# blinkenbytes_sch_altium_design.net
KiCad netlist of a schematic drawn in Altium Designer
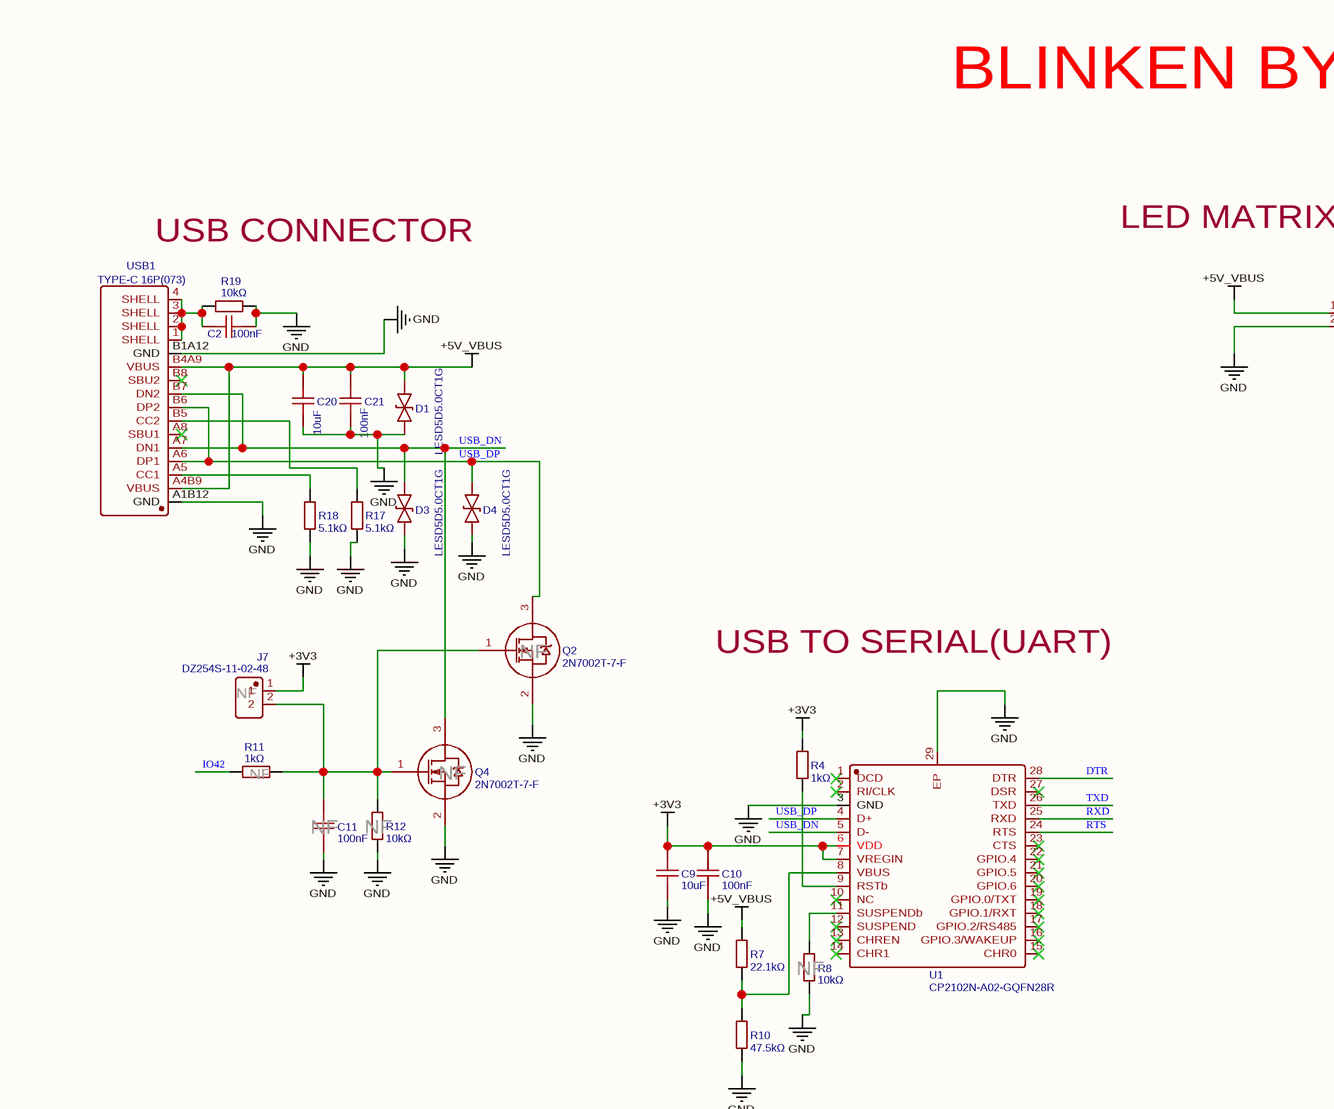
[diagram p0: blinkenbytes_sch_altium design.schdoc, top left]
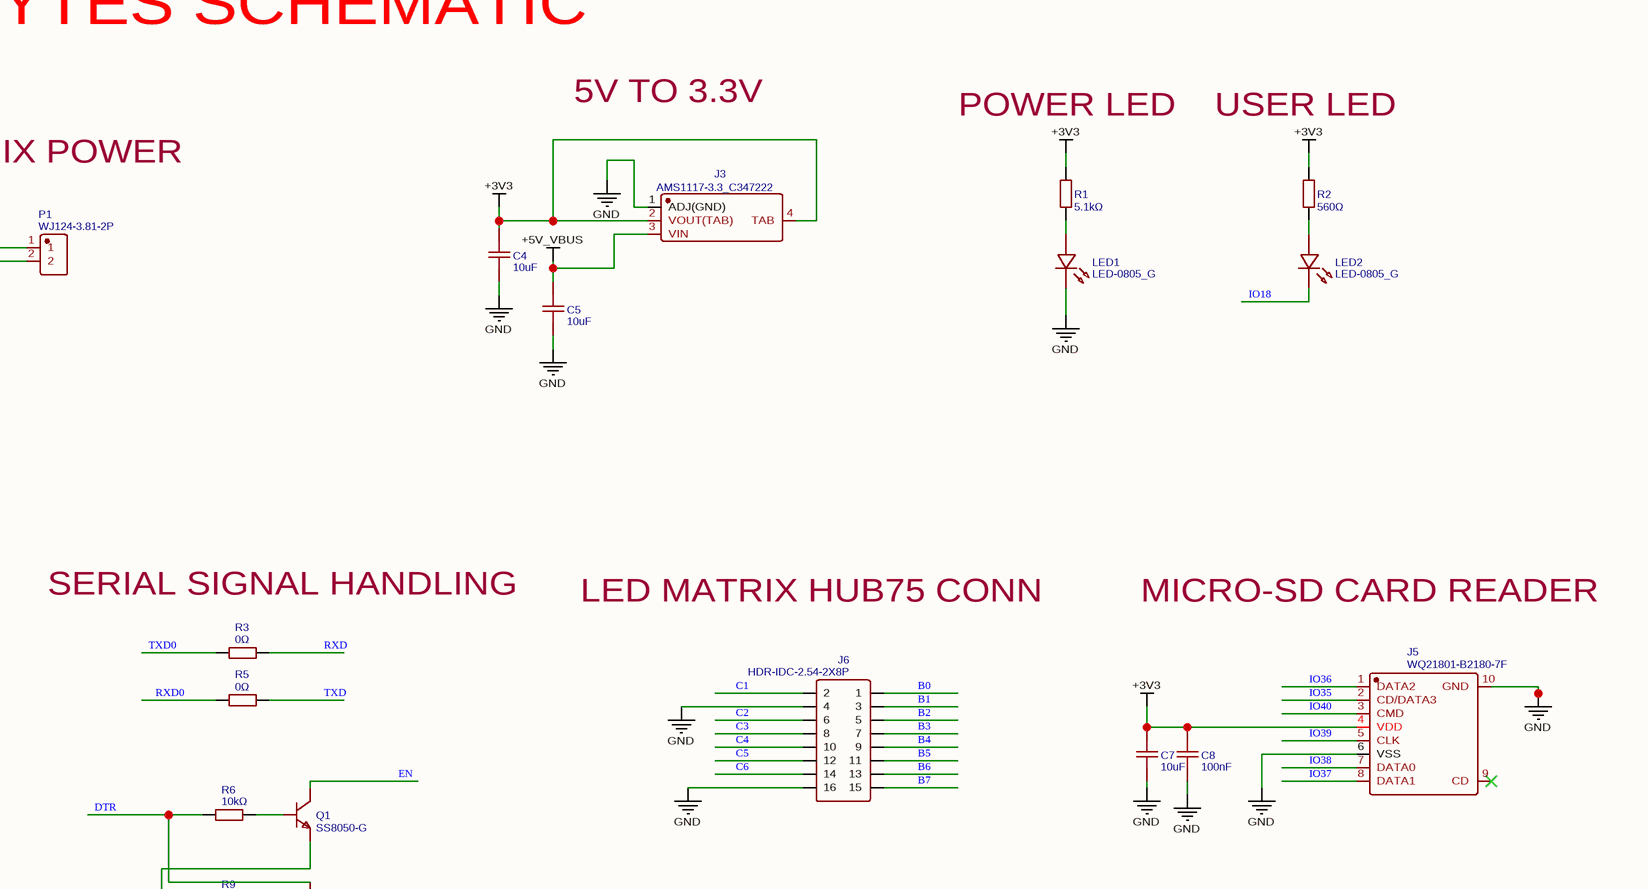
[diagram p1: blinkenbytes_sch_altium design.schdoc, top right]
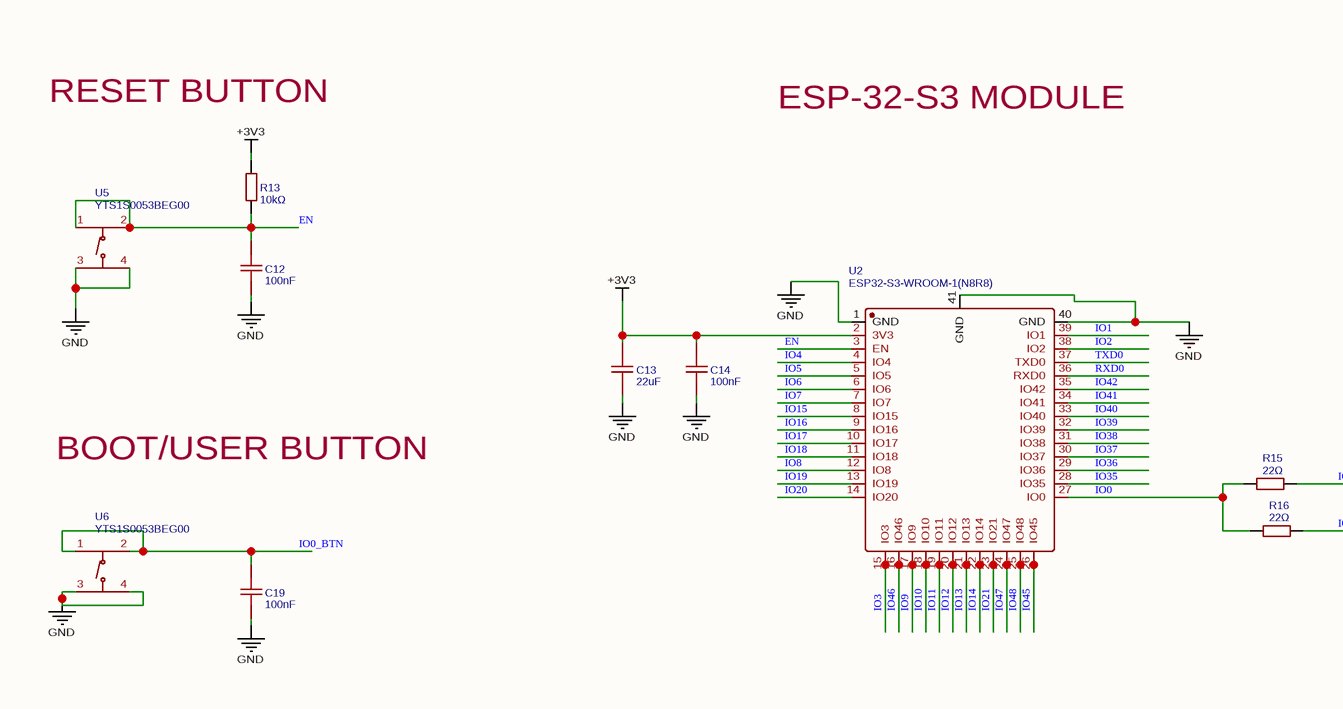
[diagram p2: blinkenbytes_sch_altium design.schdoc, bottom left]
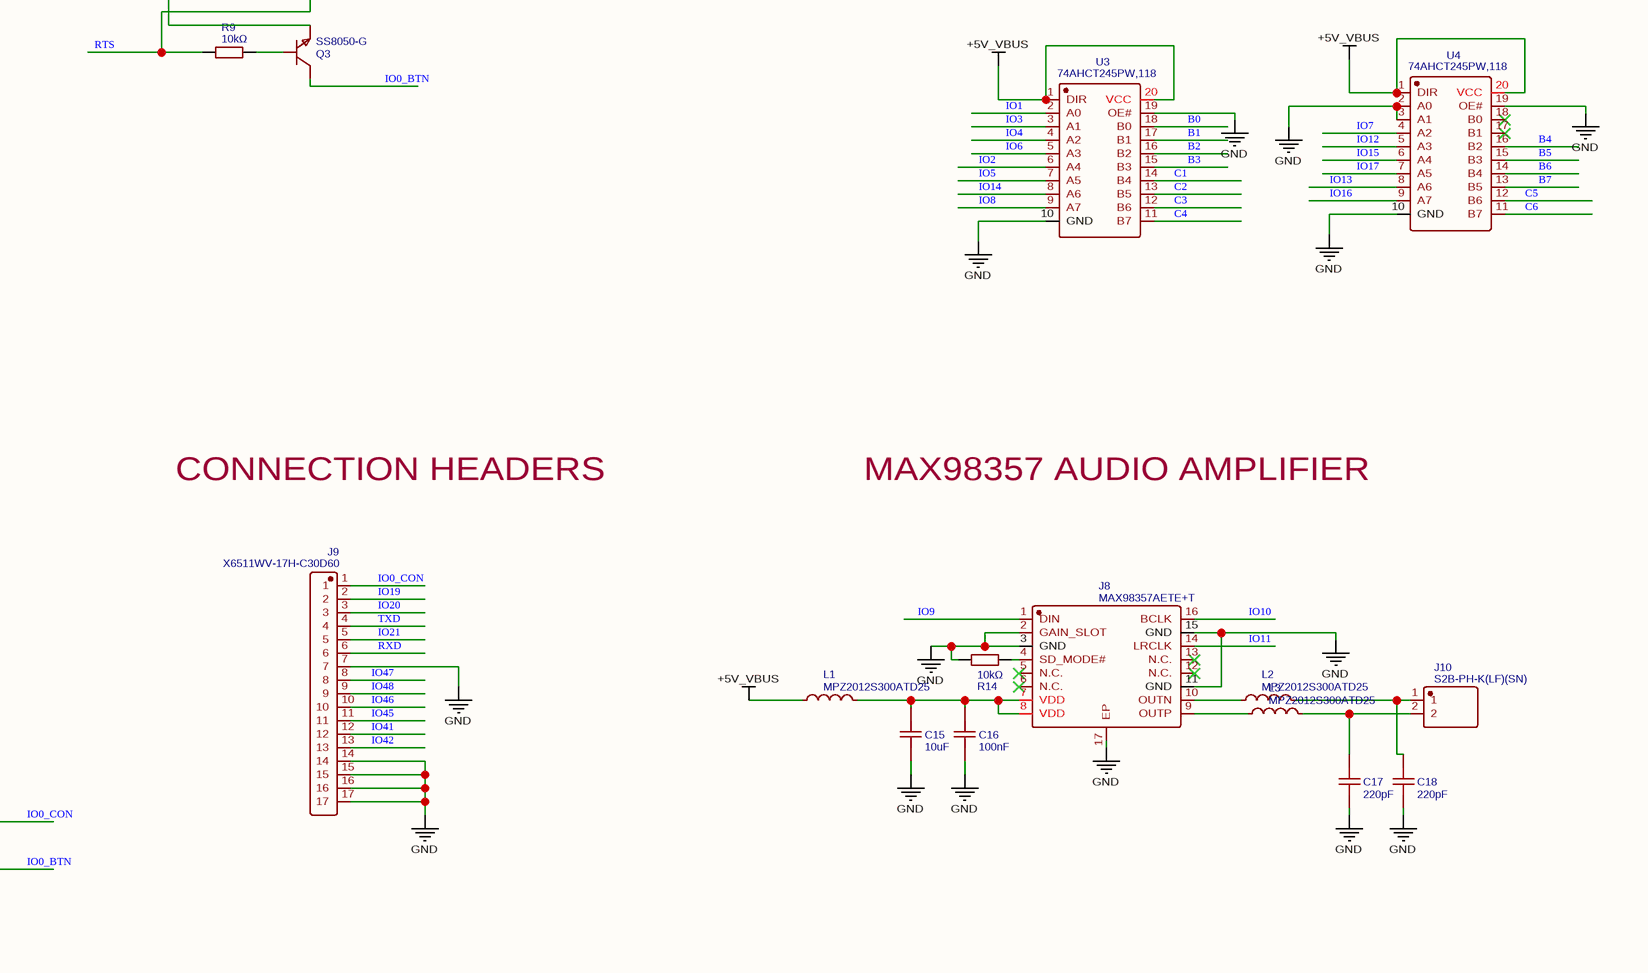
[diagram p3: blinkenbytes_sch_altium design.schdoc, bottom right]

(export (version "E")
  (design (tool "Eeschema 10.0.6"))
  (components
    (comp (ref "C2")
      (value "100nF")
      (fields
        (field (name "MANUFACTURER") "SAMSUNG(三星)")
        (field (name "MANUFACTURER PART") "CL21B104KBFWPJE")
        (field (name "CONTRIBUTOR") "lcsc")
      )
      (libsource (lib "altium-import") (part "root_0_100nF_"))
    )
    (comp (ref "C4")
      (value "10uF")
      (fields
        (field (name "MANUFACTURER") "SAMSUNG(三星)")
        (field (name "MANUFACTURER PART") "CL05A106MP5NUNC")
        (field (name "CONTRIBUTOR") "LCSC")
      )
      (libsource (lib "altium-import") (part "root_1_10uF_"))
    )
    (comp (ref "C5")
      (value "10uF")
      (fields
        (field (name "MANUFACTURER") "SAMSUNG(三星)")
        (field (name "MANUFACTURER PART") "CL05A106MP5NUNC")
        (field (name "CONTRIBUTOR") "LCSC")
      )
      (libsource (lib "altium-import") (part "root_1_10uF_"))
    )
    (comp (ref "C7")
      (value "10uF")
      (fields
        (field (name "MANUFACTURER") "SAMSUNG(三星)")
        (field (name "MANUFACTURER PART") "CL05A106MP5NUNC")
        (field (name "CONTRIBUTOR") "LCSC")
      )
      (libsource (lib "altium-import") (part "root_1_10uF_"))
    )
    (comp (ref "C8")
      (value "100nF")
      (fields
        (field (name "MANUFACTURER PART") "CL05B104KO5NNNC")
        (field (name "MANUFACTURER") "SAMSUNG(三星)")
      )
      (libsource (lib "altium-import") (part "root_1_100nF_"))
    )
    (comp (ref "C9")
      (value "10uF")
      (fields
        (field (name "MANUFACTURER") "SAMSUNG(三星)")
        (field (name "MANUFACTURER PART") "CL05A106MP5NUNC")
        (field (name "CONTRIBUTOR") "LCSC")
      )
      (libsource (lib "altium-import") (part "root_1_10uF_"))
    )
    (comp (ref "C10")
      (value "100nF")
      (fields
        (field (name "MANUFACTURER PART") "CL05B104KO5NNNC")
        (field (name "MANUFACTURER") "SAMSUNG(三星)")
      )
      (libsource (lib "altium-import") (part "root_1_100nF_"))
    )
    (comp (ref "C11")
      (value "100nF")
      (fields
        (field (name "MANUFACTURER PART") "CL05B104KO5NNNC")
        (field (name "MANUFACTURER") "SAMSUNG(三星)")
      )
      (libsource (lib "altium-import") (part "root_1_100nF_"))
    )
    (comp (ref "C12")
      (value "100nF")
      (fields
        (field (name "MANUFACTURER PART") "CL05B104KO5NNNC")
        (field (name "MANUFACTURER") "SAMSUNG(三星)")
      )
      (libsource (lib "altium-import") (part "root_1_100nF_"))
    )
    (comp (ref "C13")
      (value "22uF")
      (fields
        (field (name "MANUFACTURER") "SAMSUNG(三星)")
        (field (name "MANUFACTURER PART") "CL21A226MAQNNNE")
      )
      (libsource (lib "altium-import") (part "root_1_22uF_"))
    )
    (comp (ref "C14")
      (value "100nF")
      (fields
        (field (name "MANUFACTURER PART") "CL05B104KO5NNNC")
        (field (name "MANUFACTURER") "SAMSUNG(三星)")
      )
      (libsource (lib "altium-import") (part "root_1_100nF_"))
    )
    (comp (ref "C15")
      (value "10uF")
      (fields
        (field (name "MANUFACTURER") "SAMSUNG(三星)")
        (field (name "MANUFACTURER PART") "CL21B106KAYQNNE")
        (field (name "CONTRIBUTOR") "lcsc")
      )
      (libsource (lib "altium-import") (part "root_1_10uF_"))
    )
    (comp (ref "C16")
      (value "100nF")
      (fields
        (field (name "MANUFACTURER") "SAMSUNG(三星)")
        (field (name "MANUFACTURER PART") "CL21B104KBFWPJE")
        (field (name "CONTRIBUTOR") "lcsc")
      )
      (libsource (lib "altium-import") (part "root_1_100nF_"))
    )
    (comp (ref "C17")
      (value "220pF")
      (fields
        (field (name "MANUFACTURER") "Kyocera AVX")
        (field (name "MANUFACTURER PART") "04025A221JAT2A")
        (field (name "CONTRIBUTOR") "LCSC")
      )
      (libsource (lib "altium-import") (part "root_1_220pF_"))
    )
    (comp (ref "C18")
      (value "220pF")
      (fields
        (field (name "MANUFACTURER") "Kyocera AVX")
        (field (name "MANUFACTURER PART") "04025A221JAT2A")
        (field (name "CONTRIBUTOR") "LCSC")
      )
      (libsource (lib "altium-import") (part "root_1_220pF_"))
    )
    (comp (ref "C19")
      (value "100nF")
      (fields
        (field (name "MANUFACTURER PART") "CL05B104KO5NNNC")
        (field (name "MANUFACTURER") "SAMSUNG(三星)")
      )
      (libsource (lib "altium-import") (part "root_1_100nF_"))
    )
    (comp (ref "C20")
      (value "10uF")
      (fields
        (field (name "MANUFACTURER") "SAMSUNG(三星)")
        (field (name "MANUFACTURER PART") "CL21B106KAYQNNE")
        (field (name "CONTRIBUTOR") "lcsc")
      )
      (libsource (lib "altium-import") (part "root_1_10uF_"))
    )
    (comp (ref "C21")
      (value "100nF")
      (fields
        (field (name "MANUFACTURER") "SAMSUNG(三星)")
        (field (name "MANUFACTURER PART") "CL21B104KBFWPJE")
        (field (name "CONTRIBUTOR") "lcsc")
      )
      (libsource (lib "altium-import") (part "root_1_100nF_"))
    )
    (comp (ref "D1")
      (value "LESD5D5.0CT1G")
      (fields (field (name "MANUFACTURER") "LRC(乐山无线电)") (field (name "CONTRIBUTOR") "LCSC"))
      (libsource (lib "altium-import") (part "root_1_LESD5D5.0CT1G_"))
    )
    (comp (ref "D3")
      (value "LESD5D5.0CT1G")
      (fields (field (name "MANUFACTURER") "LRC(乐山无线电)") (field (name "CONTRIBUTOR") "LCSC"))
      (libsource (lib "altium-import") (part "root_1_LESD5D5.0CT1G_"))
    )
    (comp (ref "D4")
      (value "LESD5D5.0CT1G")
      (fields (field (name "MANUFACTURER") "LRC(乐山无线电)") (field (name "CONTRIBUTOR") "LCSC"))
      (libsource (lib "altium-import") (part "root_1_LESD5D5.0CT1G_"))
    )
    (comp (ref "J3")
      (value "AMS1117-3.3_C347222")
      (fields
        (field (name "MANUFACTURER") "UMW(友台半导体)")
        (field (name "MANUFACTURER PART") "AMS1117-3.3")
        (field (name "CONTRIBUTOR") "LCSC")
      )
      (libsource (lib "altium-import") (part "root_0_AMS1117-3.3_C347222_"))
    )
    (comp (ref "J5")
      (value "WQ21801-B2180-7F")
      (fields (field (name "MANUFACTURER") "FOXCONN(富士康)") (field (name "CONTRIBUTOR") "LCSC"))
      (libsource (lib "altium-import") (part "root_0_WQ21801-B2180-7F_"))
    )
    (comp (ref "J6")
      (value "HDR-IDC-2.54-2X8P")
      (fields (field (name "MANUFACTURER") "BOOMELE(博穆精密)") (field (name "MANUFACTURER PART") "2.54-2*8P简牛"))
      (libsource (lib "altium-import") (part "root_0_HDR-IDC-2.54-2X8P_"))
    )
    (comp (ref "J7")
      (value "DZ254S-11-02-48")
      (fields (field (name "MANUFACTURER") "DEALON(德艺隆)") (field (name "CONTRIBUTOR") "lcsc"))
      (libsource (lib "altium-import") (part "root_0_DZ254S-11-02-48_"))
    )
    (comp (ref "J8")
      (value "MAX98357AETE+T")
      (fields (field (name "MANUFACTURER") "ADI(亚德诺)/MAXIM(美信)") (field (name "CONTRIBUTOR") "LCSC"))
      (libsource (lib "altium-import") (part "root_0_MAX98357AETE+T_"))
    )
    (comp (ref "J9")
      (value "X6511WV-17H-C30D60")
      (fields
        (field (name "MANUFACTURER") "XKB Connection(中国星坤)")
        (field (name "MANUFACTURER PART") "X6511WV-17H-C60D30")
        (field (name "CONTRIBUTOR") "LCSC")
      )
      (libsource (lib "altium-import") (part "root_0_X6511WV-17H-C30D60_"))
    )
    (comp (ref "J10")
      (value "S2B-PH-K(LF)(SN)")
      (fields (field (name "MANUFACTURER") "JST") (field (name "CONTRIBUTOR") "LCSC"))
      (libsource (lib "altium-import") (part "root_0_S2B-PH-K(LF)(SN)_"))
    )
    (comp (ref "L1")
      (value "MPZ2012S300ATD25")
      (fields (field (name "MANUFACTURER") "TDK") (field (name "CONTRIBUTOR") "LCSC"))
      (libsource (lib "altium-import") (part "root_0_MPZ2012S300ATD25_"))
    )
    (comp (ref "L2")
      (value "MPZ2012S300ATD25")
      (fields (field (name "MANUFACTURER") "TDK") (field (name "CONTRIBUTOR") "LCSC"))
      (libsource (lib "altium-import") (part "root_0_MPZ2012S300ATD25_"))
    )
    (comp (ref "L3")
      (value "MPZ2012S300ATD25")
      (fields (field (name "MANUFACTURER") "TDK") (field (name "CONTRIBUTOR") "LCSC"))
      (libsource (lib "altium-import") (part "root_0_MPZ2012S300ATD25_"))
    )
    (comp (ref "LED1")
      (value "LED-0805_G")
      (fields
        (field (name "MANUFACTURER") "国星光电")
        (field (name "MANUFACTURER PART") "NCD0805G1")
        (field (name "CONTRIBUTOR") "LCEDA_Lib")
      )
      (libsource (lib "altium-import") (part "root_3_LED-0805_G_"))
    )
    (comp (ref "LED2")
      (value "LED-0805_G")
      (fields
        (field (name "MANUFACTURER") "国星光电")
        (field (name "MANUFACTURER PART") "NCD0805G1")
        (field (name "CONTRIBUTOR") "LCEDA_Lib")
      )
      (libsource (lib "altium-import") (part "root_3_LED-0805_G_"))
    )
    (comp (ref "P1")
      (value "WJ124-3.81-2P")
      (fields (field (name "MANUFACTURER") "KANGNEX(康奈克斯电气)"))
      (libsource (lib "altium-import") (part "root_0_WJ124-3.81-2P_"))
    )
    (comp (ref "Q1")
      (value "SS8050-G")
      (fields
        (field (name "MANUFACTURER") "CJ(江苏长电/长晶)")
        (field (name "MANUFACTURER PART") "SS8050-G(RANGE:120-200)")
        (field (name "CONTRIBUTOR") "LCSC")
      )
      (libsource (lib "altium-import") (part "root_0_SS8050-G_"))
    )
    (comp (ref "Q2")
      (value "2N7002T-7-F")
      (fields (field (name "MANUFACTURER") "DIODES(美台)") (field (name "CONTRIBUTOR") "LCSC"))
      (libsource (lib "altium-import") (part "root_0_2N7002T-7-F_"))
    )
    (comp (ref "Q3")
      (value "SS8050-G")
      (fields
        (field (name "MANUFACTURER") "CJ(江苏长电/长晶)")
        (field (name "MANUFACTURER PART") "SS8050-G(RANGE:120-200)")
        (field (name "CONTRIBUTOR") "LCSC")
      )
      (libsource (lib "") (part "root_0_SS8050-G__1"))
    )
    (comp (ref "Q4")
      (value "2N7002T-7-F")
      (fields (field (name "MANUFACTURER") "DIODES(美台)") (field (name "CONTRIBUTOR") "LCSC"))
      (libsource (lib "altium-import") (part "root_0_2N7002T-7-F_"))
    )
    (comp (ref "R1")
      (value "5.1kΩ")
      (fields
        (field (name "MANUFACTURER") "UNI-ROYAL(厚声)")
        (field (name "MANUFACTURER PART") "0402WGF5101TCE")
      )
      (libsource (lib "altium-import") (part "root_1_5.1kΩ_"))
    )
    (comp (ref "R2")
      (value "560Ω")
      (fields
        (field (name "MANUFACTURER") "UNI-ROYAL(厚声)")
        (field (name "MANUFACTURER PART") "0402WGF5600TCE")
      )
      (libsource (lib "altium-import") (part "root_1_560Ω_"))
    )
    (comp (ref "R3")
      (value "0Ω")
      (fields
        (field (name "MANUFACTURER") "UNI-ROYAL(厚声)")
        (field (name "MANUFACTURER PART") "0402WGF0000TCE")
      )
      (libsource (lib "altium-import") (part "root_0_0Ω_"))
    )
    (comp (ref "R4")
      (value "1kΩ")
      (fields
        (field (name "MANUFACTURER") "UNI-ROYAL(厚声)")
        (field (name "MANUFACTURER PART") "0402WGF1001TCE")
      )
      (libsource (lib "altium-import") (part "root_1_1kΩ_"))
    )
    (comp (ref "R5")
      (value "0Ω")
      (fields
        (field (name "MANUFACTURER") "UNI-ROYAL(厚声)")
        (field (name "MANUFACTURER PART") "0402WGF0000TCE")
      )
      (libsource (lib "altium-import") (part "root_0_0Ω_"))
    )
    (comp (ref "R6")
      (value "10kΩ")
      (fields
        (field (name "MANUFACTURER") "UNI-ROYAL(厚声)")
        (field (name "MANUFACTURER PART") "0402WGF1002TCE")
      )
      (libsource (lib "altium-import") (part "root_0_10kΩ_"))
    )
    (comp (ref "R7")
      (value "22.1kΩ")
      (fields
        (field (name "MANUFACTURER") "UNI-ROYAL(厚声)")
        (field (name "MANUFACTURER PART") "0402WGF2212TCE")
      )
      (libsource (lib "altium-import") (part "root_1_22.1kΩ_"))
    )
    (comp (ref "R8")
      (value "10kΩ")
      (fields
        (field (name "MANUFACTURER") "UNI-ROYAL(厚声)")
        (field (name "MANUFACTURER PART") "0402WGF1002TCE")
      )
      (libsource (lib "altium-import") (part "root_3_10kΩ_"))
    )
    (comp (ref "R9")
      (value "10kΩ")
      (fields
        (field (name "MANUFACTURER") "UNI-ROYAL(厚声)")
        (field (name "MANUFACTURER PART") "0402WGF1002TCE")
      )
      (libsource (lib "altium-import") (part "root_0_10kΩ_"))
    )
    (comp (ref "R10")
      (value "47.5kΩ")
      (fields
        (field (name "MANUFACTURER") "UNI-ROYAL(厚声)")
        (field (name "MANUFACTURER PART") "0402WGF4752TCE")
      )
      (libsource (lib "altium-import") (part "root_1_47.5kΩ_"))
    )
    (comp (ref "R11")
      (value "1kΩ")
      (fields
        (field (name "MANUFACTURER") "UNI-ROYAL(厚声)")
        (field (name "MANUFACTURER PART") "0402WGF1001TCE")
      )
      (libsource (lib "altium-import") (part "root_2_1kΩ_"))
    )
    (comp (ref "R12")
      (value "10kΩ")
      (fields
        (field (name "MANUFACTURER") "UNI-ROYAL(厚声)")
        (field (name "MANUFACTURER PART") "0402WGF1002TCE")
      )
      (libsource (lib "altium-import") (part "root_3_10kΩ_"))
    )
    (comp (ref "R13")
      (value "10kΩ")
      (fields
        (field (name "MANUFACTURER") "UNI-ROYAL(厚声)")
        (field (name "MANUFACTURER PART") "0402WGF1002TCE")
      )
      (libsource (lib "altium-import") (part "root_1_10kΩ_"))
    )
    (comp (ref "R14")
      (value "10kΩ")
      (fields
        (field (name "MANUFACTURER") "UNI-ROYAL(厚声)")
        (field (name "MANUFACTURER PART") "0402WGF1002TCE")
      )
      (libsource (lib "altium-import") (part "root_0_10kΩ_"))
    )
    (comp (ref "R15")
      (value "22Ω")
      (fields
        (field (name "MANUFACTURER") "UNI-ROYAL(厚声)")
        (field (name "MANUFACTURER PART") "0402WGF220JTCE")
      )
      (libsource (lib "altium-import") (part "root_0_22Ω_"))
    )
    (comp (ref "R16")
      (value "22Ω")
      (fields
        (field (name "MANUFACTURER") "UNI-ROYAL(厚声)")
        (field (name "MANUFACTURER PART") "0402WGF220JTCE")
      )
      (libsource (lib "altium-import") (part "root_0_22Ω_"))
    )
    (comp (ref "R17")
      (value "5.1kΩ")
      (fields
        (field (name "MANUFACTURER") "UNI-ROYAL(厚声)")
        (field (name "MANUFACTURER PART") "0402WGF5101TCE")
      )
      (libsource (lib "altium-import") (part "root_1_5.1kΩ_"))
    )
    (comp (ref "R18")
      (value "5.1kΩ")
      (fields
        (field (name "MANUFACTURER") "UNI-ROYAL(厚声)")
        (field (name "MANUFACTURER PART") "0402WGF5101TCE")
      )
      (libsource (lib "altium-import") (part "root_1_5.1kΩ_"))
    )
    (comp (ref "R19")
      (value "10kΩ")
      (fields
        (field (name "MANUFACTURER") "UNI-ROYAL(厚声)")
        (field (name "MANUFACTURER PART") "0603WAF1002T5E")
      )
      (libsource (lib "altium-import") (part "root_0_10kΩ_"))
    )
    (comp (ref "U1")
      (value "CP2102N-A02-GQFN28R")
      (fields (field (name "MANUFACTURER") "SKYWORKS/SILICON LABS(芯科)") (field (name "CONTRIBUTOR") "LCSC"))
      (libsource (lib "altium-import") (part "root_0_CP2102N-A02-GQFN28R_"))
    )
    (comp (ref "U2")
      (value "ESP32-S3-WROOM-1(N8R8)")
      (fields
        (field (name "MANUFACTURER") "ESPRESSIF(乐鑫)")
        (field (name "MANUFACTURER PART") "ESP32-S3-WROOM-1-N8R8")
        (field (name "CONTRIBUTOR") "LCSC")
      )
      (libsource (lib "altium-import") (part "root_0_ESP32-S3-WROOM-1(N8R8)_"))
    )
    (comp (ref "U3")
      (value "74AHCT245PW,118")
      (fields (field (name "MANUFACTURER") "Nexperia(安世)") (field (name "CONTRIBUTOR") "LCSC"))
      (libsource (lib "altium-import") (part "root_0_74AHCT245PW,118_"))
    )
    (comp (ref "U4")
      (value "74AHCT245PW,118")
      (fields (field (name "MANUFACTURER") "Nexperia(安世)") (field (name "CONTRIBUTOR") "LCSC"))
      (libsource (lib "altium-import") (part "root_0_74AHCT245PW,118_"))
    )
    (comp (ref "U5")
      (value "YTS1S0053BEG00")
      (fields (field (name "MANUFACTURER") "YIYUAN(怡远)") (field (name "CONTRIBUTOR") "lcsc"))
      (libsource (lib "altium-import") (part "root_0_YTS1S0053BEG00_"))
    )
    (comp (ref "U6")
      (value "YTS1S0053BEG00")
      (fields (field (name "MANUFACTURER") "YIYUAN(怡远)") (field (name "CONTRIBUTOR") "lcsc"))
      (libsource (lib "altium-import") (part "root_0_YTS1S0053BEG00_"))
    )
    (comp (ref "USB1")
      (value "TYPE-C 16P(073)")
      (fields (field (name "MANUFACTURER") "SHOU HAN(首韩)") (field (name "CONTRIBUTOR") "LCSC"))
      (libsource (lib "altium-import") (part "root_2_TYPE-C 16P(073)_"))
    )
  )
  (nets
    (net (code "1") (name "+3V3") (class "Default")
      (node (ref "C10") (pin "2") (pinfunction "2_2") (pintype "passive"))
      (node (ref "C13") (pin "2") (pinfunction "2_2") (pintype "passive"))
      (node (ref "C14") (pin "2") (pinfunction "2_2") (pintype "passive"))
      (node (ref "C4") (pin "2") (pinfunction "2_2") (pintype "passive"))
      (node (ref "C7") (pin "2") (pinfunction "2_2") (pintype "passive"))
      (node (ref "C8") (pin "2") (pinfunction "2_2") (pintype "passive"))
      (node (ref "C9") (pin "2") (pinfunction "2_2") (pintype "passive"))
      (node (ref "J3") (pin "2") (pinfunction "VOUT(TAB)_2") (pintype "passive"))
      (node (ref "J3") (pin "4") (pinfunction "TAB_4") (pintype "passive"))
      (node (ref "J5") (pin "4") (pinfunction "VDD_4") (pintype "passive"))
      (node (ref "J7") (pin "1") (pinfunction "1_1") (pintype "passive"))
      (node (ref "R1") (pin "2") (pinfunction "2_2") (pintype "passive"))
      (node (ref "R13") (pin "2") (pinfunction "2_2") (pintype "passive"))
      (node (ref "R2") (pin "2") (pinfunction "2_2") (pintype "passive"))
      (node (ref "R4") (pin "2") (pinfunction "2_2") (pintype "passive"))
      (node (ref "U1") (pin "6") (pinfunction "VDD_6") (pintype "passive"))
      (node (ref "U1") (pin "7") (pinfunction "VREGIN_7") (pintype "passive"))
      (node (ref "U2") (pin "2") (pinfunction "3V3_2") (pintype "passive"))
    )
    (net (code "2") (name "+5V_VBUS") (class "Default")
      (node (ref "C20") (pin "2") (pinfunction "2_2") (pintype "passive"))
      (node (ref "C21") (pin "2") (pinfunction "2_2") (pintype "passive"))
      (node (ref "C5") (pin "2") (pinfunction "2_2") (pintype "passive"))
      (node (ref "D1") (pin "1") (pinfunction "1_1") (pintype "passive"))
      (node (ref "J3") (pin "3") (pinfunction "VIN_3") (pintype "passive"))
      (node (ref "L1") (pin "1") (pinfunction "1_1") (pintype "passive"))
      (node (ref "P1") (pin "1") (pinfunction "1_1") (pintype "passive"))
      (node (ref "R7") (pin "2") (pinfunction "2_2") (pintype "passive"))
      (node (ref "U3") (pin "1") (pinfunction "DIR_1") (pintype "passive"))
      (node (ref "U3") (pin "20") (pinfunction "VCC_20") (pintype "passive"))
      (node (ref "U4") (pin "1") (pinfunction "DIR_1") (pintype "passive"))
      (node (ref "U4") (pin "20") (pinfunction "VCC_20") (pintype "passive"))
      (node (ref "USB1") (pin "A4B9") (pinfunction "VBUS_A4B9") (pintype "passive"))
      (node (ref "USB1") (pin "B4A9") (pinfunction "VBUS_B4A9") (pintype "passive"))
    )
    (net (code "3") (name "/B0") (class "Default")
      (node (ref "J6") (pin "1") (pinfunction "1_1") (pintype "passive"))
      (node (ref "U3") (pin "18") (pinfunction "B0_18") (pintype "passive"))
    )
    (net (code "4") (name "/B1") (class "Default")
      (node (ref "J6") (pin "3") (pinfunction "3_3") (pintype "passive"))
      (node (ref "U3") (pin "17") (pinfunction "B1_17") (pintype "passive"))
    )
    (net (code "5") (name "/B2") (class "Default")
      (node (ref "J6") (pin "5") (pinfunction "5_5") (pintype "passive"))
      (node (ref "U3") (pin "16") (pinfunction "B2_16") (pintype "passive"))
    )
    (net (code "6") (name "/B3") (class "Default")
      (node (ref "J6") (pin "7") (pinfunction "7_7") (pintype "passive"))
      (node (ref "U3") (pin "15") (pinfunction "B3_15") (pintype "passive"))
    )
    (net (code "7") (name "/B4") (class "Default")
      (node (ref "J6") (pin "9") (pinfunction "9_9") (pintype "passive"))
      (node (ref "U4") (pin "16") (pinfunction "B2_16") (pintype "passive"))
    )
    (net (code "8") (name "/B5") (class "Default")
      (node (ref "J6") (pin "11") (pinfunction "11_11") (pintype "passive"))
      (node (ref "U4") (pin "15") (pinfunction "B3_15") (pintype "passive"))
    )
    (net (code "9") (name "/B6") (class "Default")
      (node (ref "J6") (pin "13") (pinfunction "13_13") (pintype "passive"))
      (node (ref "U4") (pin "14") (pinfunction "B4_14") (pintype "passive"))
    )
    (net (code "10") (name "/B7") (class "Default")
      (node (ref "J6") (pin "15") (pinfunction "15_15") (pintype "passive"))
      (node (ref "U4") (pin "13") (pinfunction "B5_13") (pintype "passive"))
    )
    (net (code "11") (name "/C1") (class "Default")
      (node (ref "J6") (pin "2") (pinfunction "2_2") (pintype "passive"))
      (node (ref "U3") (pin "14") (pinfunction "B4_14") (pintype "passive"))
    )
    (net (code "12") (name "/C2") (class "Default")
      (node (ref "J6") (pin "6") (pinfunction "6_6") (pintype "passive"))
      (node (ref "U3") (pin "13") (pinfunction "B5_13") (pintype "passive"))
    )
    (net (code "13") (name "/C3") (class "Default")
      (node (ref "J6") (pin "8") (pinfunction "8_8") (pintype "passive"))
      (node (ref "U3") (pin "12") (pinfunction "B6_12") (pintype "passive"))
    )
    (net (code "14") (name "/C4") (class "Default")
      (node (ref "J6") (pin "10") (pinfunction "10_10") (pintype "passive"))
      (node (ref "U3") (pin "11") (pinfunction "B7_11") (pintype "passive"))
    )
    (net (code "15") (name "/C5") (class "Default")
      (node (ref "J6") (pin "12") (pinfunction "12_12") (pintype "passive"))
      (node (ref "U4") (pin "12") (pinfunction "B6_12") (pintype "passive"))
    )
    (net (code "16") (name "/C6") (class "Default")
      (node (ref "J6") (pin "14") (pinfunction "14_14") (pintype "passive"))
      (node (ref "U4") (pin "11") (pinfunction "B7_11") (pintype "passive"))
    )
    (net (code "17") (name "/DTR") (class "Default")
      (node (ref "Q3") (pin "2") (pinfunction "E_2") (pintype "passive"))
      (node (ref "R6") (pin "1") (pinfunction "1_1") (pintype "passive"))
      (node (ref "U1") (pin "28") (pinfunction "DTR_28") (pintype "passive"))
    )
    (net (code "18") (name "/EN") (class "Default")
      (node (ref "C12") (pin "2") (pinfunction "2_2") (pintype "passive"))
      (node (ref "Q1") (pin "3") (pinfunction "C_3") (pintype "passive"))
      (node (ref "R13") (pin "1") (pinfunction "1_1") (pintype "passive"))
      (node (ref "U2") (pin "3") (pinfunction "EN_3") (pintype "passive"))
      (node (ref "U5") (pin "1") (pinfunction "A_1") (pintype "passive"))
      (node (ref "U5") (pin "2") (pinfunction "B_2") (pintype "passive"))
    )
    (net (code "19") (name "/IO0") (class "Default")
      (node (ref "R15") (pin "1") (pinfunction "1_1") (pintype "passive"))
      (node (ref "R16") (pin "1") (pinfunction "1_1") (pintype "passive"))
      (node (ref "U2") (pin "27") (pinfunction "IO0_27") (pintype "passive"))
    )
    (net (code "20") (name "/IO0_BTN") (class "Default")
      (node (ref "C19") (pin "2") (pinfunction "2_2") (pintype "passive"))
      (node (ref "Q3") (pin "3") (pinfunction "C_3") (pintype "passive"))
      (node (ref "R16") (pin "2") (pinfunction "2_2") (pintype "passive"))
      (node (ref "U6") (pin "1") (pinfunction "A_1") (pintype "passive"))
      (node (ref "U6") (pin "2") (pinfunction "B_2") (pintype "passive"))
    )
    (net (code "21") (name "/IO0_CON") (class "Default")
      (node (ref "J9") (pin "1") (pinfunction "1_1") (pintype "passive"))
      (node (ref "R15") (pin "2") (pinfunction "2_2") (pintype "passive"))
    )
    (net (code "22") (name "/IO1") (class "Default")
      (node (ref "U2") (pin "39") (pinfunction "IO1_39") (pintype "passive"))
      (node (ref "U3") (pin "2") (pinfunction "A0_2") (pintype "passive"))
    )
    (net (code "23") (name "/IO2") (class "Default")
      (node (ref "U2") (pin "38") (pinfunction "IO2_38") (pintype "passive"))
      (node (ref "U3") (pin "6") (pinfunction "A4_6") (pintype "passive"))
    )
    (net (code "24") (name "/IO3") (class "Default")
      (node (ref "U2") (pin "15") (pinfunction "IO3_15") (pintype "passive"))
      (node (ref "U3") (pin "3") (pinfunction "A1_3") (pintype "passive"))
    )
    (net (code "25") (name "/IO4") (class "Default")
      (node (ref "U2") (pin "4") (pinfunction "IO4_4") (pintype "passive"))
      (node (ref "U3") (pin "4") (pinfunction "A2_4") (pintype "passive"))
    )
    (net (code "26") (name "/IO5") (class "Default")
      (node (ref "U2") (pin "5") (pinfunction "IO5_5") (pintype "passive"))
      (node (ref "U3") (pin "7") (pinfunction "A5_7") (pintype "passive"))
    )
    (net (code "27") (name "/IO6") (class "Default")
      (node (ref "U2") (pin "6") (pinfunction "IO6_6") (pintype "passive"))
      (node (ref "U3") (pin "5") (pinfunction "A3_5") (pintype "passive"))
    )
    (net (code "28") (name "/IO7") (class "Default")
      (node (ref "U2") (pin "7") (pinfunction "IO7_7") (pintype "passive"))
      (node (ref "U4") (pin "4") (pinfunction "A2_4") (pintype "passive"))
    )
    (net (code "29") (name "/IO8") (class "Default")
      (node (ref "U2") (pin "12") (pinfunction "IO8_12") (pintype "passive"))
      (node (ref "U3") (pin "9") (pinfunction "A7_9") (pintype "passive"))
    )
    (net (code "30") (name "/IO9") (class "Default")
      (node (ref "J8") (pin "1") (pinfunction "DIN_1") (pintype "passive"))
      (node (ref "U2") (pin "17") (pinfunction "IO9_17") (pintype "passive"))
    )
    (net (code "31") (name "/IO10") (class "Default")
      (node (ref "J8") (pin "16") (pinfunction "BCLK_16") (pintype "passive"))
      (node (ref "U2") (pin "18") (pinfunction "IO10_18") (pintype "passive"))
    )
    (net (code "32") (name "/IO11") (class "Default")
      (node (ref "J8") (pin "14") (pinfunction "LRCLK_14") (pintype "passive"))
      (node (ref "U2") (pin "19") (pinfunction "IO11_19") (pintype "passive"))
    )
    (net (code "33") (name "/IO12") (class "Default")
      (node (ref "U2") (pin "20") (pinfunction "IO12_20") (pintype "passive"))
      (node (ref "U4") (pin "5") (pinfunction "A3_5") (pintype "passive"))
    )
    (net (code "34") (name "/IO13") (class "Default")
      (node (ref "U2") (pin "21") (pinfunction "IO13_21") (pintype "passive"))
      (node (ref "U4") (pin "8") (pinfunction "A6_8") (pintype "passive"))
    )
    (net (code "35") (name "/IO14") (class "Default")
      (node (ref "U2") (pin "22") (pinfunction "IO14_22") (pintype "passive"))
      (node (ref "U3") (pin "8") (pinfunction "A6_8") (pintype "passive"))
    )
    (net (code "36") (name "/IO15") (class "Default")
      (node (ref "U2") (pin "8") (pinfunction "IO15_8") (pintype "passive"))
      (node (ref "U4") (pin "6") (pinfunction "A4_6") (pintype "passive"))
    )
    (net (code "37") (name "/IO16") (class "Default")
      (node (ref "U2") (pin "9") (pinfunction "IO16_9") (pintype "passive"))
      (node (ref "U4") (pin "9") (pinfunction "A7_9") (pintype "passive"))
    )
    (net (code "38") (name "/IO17") (class "Default")
      (node (ref "U2") (pin "10") (pinfunction "IO17_10") (pintype "passive"))
      (node (ref "U4") (pin "7") (pinfunction "A5_7") (pintype "passive"))
    )
    (net (code "39") (name "/IO18") (class "Default")
      (node (ref "LED2") (pin "2") (pinfunction "2_2") (pintype "passive"))
      (node (ref "U2") (pin "11") (pinfunction "IO18_11") (pintype "passive"))
    )
    (net (code "40") (name "/IO19") (class "Default")
      (node (ref "J9") (pin "2") (pinfunction "2_2") (pintype "passive"))
      (node (ref "U2") (pin "13") (pinfunction "IO19_13") (pintype "passive"))
    )
    (net (code "41") (name "/IO20") (class "Default")
      (node (ref "J9") (pin "3") (pinfunction "3_3") (pintype "passive"))
      (node (ref "U2") (pin "14") (pinfunction "IO20_14") (pintype "passive"))
    )
    (net (code "42") (name "/IO21") (class "Default")
      (node (ref "J9") (pin "5") (pinfunction "5_5") (pintype "passive"))
      (node (ref "U2") (pin "23") (pinfunction "IO21_23") (pintype "passive"))
    )
    (net (code "43") (name "/IO35") (class "Default")
      (node (ref "J5") (pin "2") (pinfunction "CD/DATA3_2") (pintype "passive"))
      (node (ref "U2") (pin "28") (pinfunction "IO35_28") (pintype "passive"))
    )
    (net (code "44") (name "/IO36") (class "Default")
      (node (ref "J5") (pin "1") (pinfunction "DATA2_1") (pintype "passive"))
      (node (ref "U2") (pin "29") (pinfunction "IO36_29") (pintype "passive"))
    )
    (net (code "45") (name "/IO37") (class "Default")
      (node (ref "J5") (pin "8") (pinfunction "DATA1_8") (pintype "passive"))
      (node (ref "U2") (pin "30") (pinfunction "IO37_30") (pintype "passive"))
    )
    (net (code "46") (name "/IO38") (class "Default")
      (node (ref "J5") (pin "7") (pinfunction "DATA0_7") (pintype "passive"))
      (node (ref "U2") (pin "31") (pinfunction "IO38_31") (pintype "passive"))
    )
    (net (code "47") (name "/IO39") (class "Default")
      (node (ref "J5") (pin "5") (pinfunction "CLK_5") (pintype "passive"))
      (node (ref "U2") (pin "32") (pinfunction "IO39_32") (pintype "passive"))
    )
    (net (code "48") (name "/IO40") (class "Default")
      (node (ref "J5") (pin "3") (pinfunction "CMD_3") (pintype "passive"))
      (node (ref "U2") (pin "33") (pinfunction "IO40_33") (pintype "passive"))
    )
    (net (code "49") (name "/IO41") (class "Default")
      (node (ref "J9") (pin "12") (pinfunction "12_12") (pintype "passive"))
      (node (ref "U2") (pin "34") (pinfunction "IO41_34") (pintype "passive"))
    )
    (net (code "50") (name "/IO42") (class "Default")
      (node (ref "J9") (pin "13") (pinfunction "13_13") (pintype "passive"))
      (node (ref "R11") (pin "2") (pinfunction "2_2") (pintype "passive"))
      (node (ref "U2") (pin "35") (pinfunction "IO42_35") (pintype "passive"))
    )
    (net (code "51") (name "/IO45") (class "Default")
      (node (ref "J9") (pin "11") (pinfunction "11_11") (pintype "passive"))
      (node (ref "U2") (pin "26") (pinfunction "IO45_26") (pintype "passive"))
    )
    (net (code "52") (name "/IO46") (class "Default")
      (node (ref "J9") (pin "10") (pinfunction "10_10") (pintype "passive"))
      (node (ref "U2") (pin "16") (pinfunction "IO46_16") (pintype "passive"))
    )
    (net (code "53") (name "/IO47") (class "Default")
      (node (ref "J9") (pin "8") (pinfunction "8_8") (pintype "passive"))
      (node (ref "U2") (pin "24") (pinfunction "IO47_24") (pintype "passive"))
    )
    (net (code "54") (name "/IO48") (class "Default")
      (node (ref "J9") (pin "9") (pinfunction "9_9") (pintype "passive"))
      (node (ref "U2") (pin "25") (pinfunction "IO48_25") (pintype "passive"))
    )
    (net (code "55") (name "/RTS") (class "Default")
      (node (ref "Q1") (pin "2") (pinfunction "E_2") (pintype "passive"))
      (node (ref "R9") (pin "1") (pinfunction "1_1") (pintype "passive"))
      (node (ref "U1") (pin "24") (pinfunction "RTS_24") (pintype "passive"))
    )
    (net (code "56") (name "/RXD") (class "Default")
      (node (ref "J9") (pin "6") (pinfunction "6_6") (pintype "passive"))
      (node (ref "R3") (pin "2") (pinfunction "2_2") (pintype "passive"))
      (node (ref "U1") (pin "25") (pinfunction "RXD_25") (pintype "passive"))
    )
    (net (code "57") (name "/RXD0") (class "Default")
      (node (ref "R5") (pin "1") (pinfunction "1_1") (pintype "passive"))
      (node (ref "U2") (pin "36") (pinfunction "RXD0_36") (pintype "passive"))
    )
    (net (code "58") (name "/TXD") (class "Default")
      (node (ref "J9") (pin "4") (pinfunction "4_4") (pintype "passive"))
      (node (ref "R5") (pin "2") (pinfunction "2_2") (pintype "passive"))
      (node (ref "U1") (pin "26") (pinfunction "TXD_26") (pintype "passive"))
    )
    (net (code "59") (name "/TXD0") (class "Default")
      (node (ref "R3") (pin "1") (pinfunction "1_1") (pintype "passive"))
      (node (ref "U2") (pin "37") (pinfunction "TXD0_37") (pintype "passive"))
    )
    (net (code "60") (name "/USB_DN") (class "Default")
      (node (ref "D3") (pin "1") (pinfunction "1_1") (pintype "passive"))
      (node (ref "Q4") (pin "3") (pinfunction "D_3") (pintype "passive"))
      (node (ref "U1") (pin "5") (pinfunction "D-_5") (pintype "passive"))
      (node (ref "USB1") (pin "A7") (pinfunction "DN1_A7") (pintype "passive"))
      (node (ref "USB1") (pin "B7") (pinfunction "DN2_B7") (pintype "passive"))
    )
    (net (code "61") (name "/USB_DP") (class "Default")
      (node (ref "D4") (pin "1") (pinfunction "1_1") (pintype "passive"))
      (node (ref "Q2") (pin "3") (pinfunction "D_3") (pintype "passive"))
      (node (ref "U1") (pin "4") (pinfunction "D+_4") (pintype "passive"))
      (node (ref "USB1") (pin "A6") (pinfunction "DP1_A6") (pintype "passive"))
      (node (ref "USB1") (pin "B6") (pinfunction "DP2_B6") (pintype "passive"))
    )
    (net (code "62") (name "GND") (class "Default")
      (node (ref "C10") (pin "1") (pinfunction "1_1") (pintype "passive"))
      (node (ref "C11") (pin "1") (pinfunction "1_1") (pintype "passive"))
      (node (ref "C12") (pin "1") (pinfunction "1_1") (pintype "passive"))
      (node (ref "C13") (pin "1") (pinfunction "1_1") (pintype "passive"))
      (node (ref "C14") (pin "1") (pinfunction "1_1") (pintype "passive"))
      (node (ref "C15") (pin "1") (pinfunction "1_1") (pintype "passive"))
      (node (ref "C16") (pin "1") (pinfunction "1_1") (pintype "passive"))
      (node (ref "C17") (pin "1") (pinfunction "1_1") (pintype "passive"))
      (node (ref "C18") (pin "1") (pinfunction "1_1") (pintype "passive"))
      (node (ref "C19") (pin "1") (pinfunction "1_1") (pintype "passive"))
      (node (ref "C2") (pin "2") (pinfunction "2_2") (pintype "passive"))
      (node (ref "C20") (pin "1") (pinfunction "1_1") (pintype "passive"))
      (node (ref "C21") (pin "1") (pinfunction "1_1") (pintype "passive"))
      (node (ref "C4") (pin "1") (pinfunction "1_1") (pintype "passive"))
      (node (ref "C5") (pin "1") (pinfunction "1_1") (pintype "passive"))
      (node (ref "C7") (pin "1") (pinfunction "1_1") (pintype "passive"))
      (node (ref "C8") (pin "1") (pinfunction "1_1") (pintype "passive"))
      (node (ref "C9") (pin "1") (pinfunction "1_1") (pintype "passive"))
      (node (ref "D1") (pin "2") (pinfunction "2_2") (pintype "passive"))
      (node (ref "D3") (pin "2") (pinfunction "2_2") (pintype "passive"))
      (node (ref "D4") (pin "2") (pinfunction "2_2") (pintype "passive"))
      (node (ref "J3") (pin "1") (pinfunction "ADJ(GND)_1") (pintype "passive"))
      (node (ref "J5") (pin "10") (pinfunction "GND_10") (pintype "passive"))
      (node (ref "J5") (pin "6") (pinfunction "VSS_6") (pintype "passive"))
      (node (ref "J6") (pin "16") (pinfunction "16_16") (pintype "passive"))
      (node (ref "J6") (pin "4") (pinfunction "4_4") (pintype "passive"))
      (node (ref "J8") (pin "11") (pinfunction "GND_11") (pintype "passive"))
      (node (ref "J8") (pin "15") (pinfunction "GND_15") (pintype "passive"))
      (node (ref "J8") (pin "17") (pinfunction "EP_17") (pintype "passive"))
      (node (ref "J8") (pin "2") (pinfunction "GAIN_SLOT_2") (pintype "passive"))
      (node (ref "J8") (pin "3") (pinfunction "GND_3") (pintype "passive"))
      (node (ref "J9") (pin "14") (pinfunction "14_14") (pintype "passive"))
      (node (ref "J9") (pin "15") (pinfunction "15_15") (pintype "passive"))
      (node (ref "J9") (pin "16") (pinfunction "16_16") (pintype "passive"))
      (node (ref "J9") (pin "17") (pinfunction "17_17") (pintype "passive"))
      (node (ref "J9") (pin "7") (pinfunction "7_7") (pintype "passive"))
      (node (ref "LED1") (pin "2") (pinfunction "2_2") (pintype "passive"))
      (node (ref "P1") (pin "2") (pinfunction "2_2") (pintype "passive"))
      (node (ref "Q2") (pin "2") (pinfunction "S_2") (pintype "passive"))
      (node (ref "Q4") (pin "2") (pinfunction "S_2") (pintype "passive"))
      (node (ref "R10") (pin "1") (pinfunction "1_1") (pintype "passive"))
      (node (ref "R12") (pin "2") (pinfunction "2_2") (pintype "passive"))
      (node (ref "R14") (pin "1") (pinfunction "1_1") (pintype "passive"))
      (node (ref "R17") (pin "1") (pinfunction "1_1") (pintype "passive"))
      (node (ref "R18") (pin "1") (pinfunction "1_1") (pintype "passive"))
      (node (ref "R19") (pin "2") (pinfunction "2_2") (pintype "passive"))
      (node (ref "R8") (pin "2") (pinfunction "2_2") (pintype "passive"))
      (node (ref "U1") (pin "29") (pinfunction "EP_29") (pintype "passive"))
      (node (ref "U1") (pin "3") (pinfunction "GND_3") (pintype "passive"))
      (node (ref "U2") (pin "1") (pinfunction "GND_1") (pintype "passive"))
      (node (ref "U2") (pin "40") (pinfunction "GND_40") (pintype "passive"))
      (node (ref "U2") (pin "41") (pinfunction "GND_41") (pintype "passive"))
      (node (ref "U3") (pin "10") (pinfunction "GND_10") (pintype "passive"))
      (node (ref "U3") (pin "19") (pinfunction "OE#_19") (pintype "passive"))
      (node (ref "U4") (pin "10") (pinfunction "GND_10") (pintype "passive"))
      (node (ref "U4") (pin "19") (pinfunction "OE#_19") (pintype "passive"))
      (node (ref "U4") (pin "2") (pinfunction "A0_2") (pintype "passive"))
      (node (ref "U4") (pin "3") (pinfunction "A1_3") (pintype "passive"))
      (node (ref "U5") (pin "3") (pinfunction "C_3") (pintype "passive"))
      (node (ref "U5") (pin "4") (pinfunction "D_4") (pintype "passive"))
      (node (ref "U6") (pin "3") (pinfunction "C_3") (pintype "passive"))
      (node (ref "U6") (pin "4") (pinfunction "D_4") (pintype "passive"))
      (node (ref "USB1") (pin "A1B12") (pinfunction "GND_A1B12") (pintype "passive"))
      (node (ref "USB1") (pin "B1A12") (pinfunction "GND_B1A12") (pintype "passive"))
    )
    (net (code "63") (name "Net-(C2-Pad1)") (class "Default")
      (node (ref "C2") (pin "1") (pinfunction "1_1") (pintype "passive"))
      (node (ref "R19") (pin "1") (pinfunction "1_1") (pintype "passive"))
      (node (ref "USB1") (pin "1") (pinfunction "SHELL_1") (pintype "passive"))
      (node (ref "USB1") (pin "2") (pinfunction "SHELL_2") (pintype "passive"))
      (node (ref "USB1") (pin "3") (pinfunction "SHELL_3") (pintype "passive"))
      (node (ref "USB1") (pin "4") (pinfunction "SHELL_4") (pintype "passive"))
    )
    (net (code "64") (name "Net-(C15-Pad2)") (class "Default")
      (node (ref "C15") (pin "2") (pinfunction "2_2") (pintype "passive"))
      (node (ref "C16") (pin "2") (pinfunction "2_2") (pintype "passive"))
      (node (ref "J8") (pin "7") (pinfunction "VDD_7") (pintype "passive"))
      (node (ref "J8") (pin "8") (pinfunction "VDD_8") (pintype "passive"))
      (node (ref "L1") (pin "2") (pinfunction "2_2") (pintype "passive"))
    )
    (net (code "65") (name "Net-(C17-Pad2)") (class "Default")
      (node (ref "C17") (pin "2") (pinfunction "2_2") (pintype "passive"))
      (node (ref "J10") (pin "2") (pinfunction "2_2") (pintype "passive"))
      (node (ref "L3") (pin "2") (pinfunction "2_2") (pintype "passive"))
    )
    (net (code "66") (name "Net-(C18-Pad2)") (class "Default")
      (node (ref "C18") (pin "2") (pinfunction "2_2") (pintype "passive"))
      (node (ref "J10") (pin "1") (pinfunction "1_1") (pintype "passive"))
      (node (ref "L2") (pin "2") (pinfunction "2_2") (pintype "passive"))
    )
    (net (code "67") (name "Net-(J8-OUTN)") (class "Default")
      (node (ref "J8") (pin "10") (pinfunction "OUTN_10") (pintype "passive"))
      (node (ref "L2") (pin "1") (pinfunction "1_1") (pintype "passive"))
    )
    (net (code "68") (name "Net-(J8-OUTP)") (class "Default")
      (node (ref "J8") (pin "9") (pinfunction "OUTP_9") (pintype "passive"))
      (node (ref "L3") (pin "1") (pinfunction "1_1") (pintype "passive"))
    )
    (net (code "69") (name "Net-(J8-SD_MODE#)") (class "Default")
      (node (ref "J8") (pin "4") (pinfunction "SD_MODE#_4") (pintype "passive"))
      (node (ref "R14") (pin "2") (pinfunction "2_2") (pintype "passive"))
    )
    (net (code "70") (name "Net-(LED1-Pad1)") (class "Default")
      (node (ref "LED1") (pin "1") (pinfunction "1_1") (pintype "passive"))
      (node (ref "R1") (pin "1") (pinfunction "1_1") (pintype "passive"))
    )
    (net (code "71") (name "Net-(LED2-Pad1)") (class "Default")
      (node (ref "LED2") (pin "1") (pinfunction "1_1") (pintype "passive"))
      (node (ref "R2") (pin "1") (pinfunction "1_1") (pintype "passive"))
    )
    (net (code "72") (name "Net-(Q1-B)") (class "Default")
      (node (ref "Q1") (pin "1") (pinfunction "B_1") (pintype "passive"))
      (node (ref "R6") (pin "2") (pinfunction "2_2") (pintype "passive"))
    )
    (net (code "73") (name "Net-(Q2-G)") (class "Default")
      (node (ref "C11") (pin "2") (pinfunction "2_2") (pintype "passive"))
      (node (ref "J7") (pin "2") (pinfunction "2_2") (pintype "passive"))
      (node (ref "Q2") (pin "1") (pinfunction "G_1") (pintype "passive"))
      (node (ref "Q4") (pin "1") (pinfunction "G_1") (pintype "passive"))
      (node (ref "R11") (pin "1") (pinfunction "1_1") (pintype "passive"))
      (node (ref "R12") (pin "1") (pinfunction "1_1") (pintype "passive"))
    )
    (net (code "74") (name "Net-(Q3-B)") (class "Default")
      (node (ref "Q3") (pin "1") (pinfunction "B_1") (pintype "passive"))
      (node (ref "R9") (pin "2") (pinfunction "2_2") (pintype "passive"))
    )
    (net (code "75") (name "Net-(U1-RSTb)") (class "Default")
      (node (ref "R4") (pin "1") (pinfunction "1_1") (pintype "passive"))
      (node (ref "U1") (pin "9") (pinfunction "RSTb_9") (pintype "passive"))
    )
    (net (code "76") (name "Net-(U1-SUSPENDb)") (class "Default")
      (node (ref "R8") (pin "1") (pinfunction "1_1") (pintype "passive"))
      (node (ref "U1") (pin "11") (pinfunction "SUSPENDb_11") (pintype "passive"))
    )
    (net (code "77") (name "Net-(U1-VBUS)") (class "Default")
      (node (ref "R10") (pin "2") (pinfunction "2_2") (pintype "passive"))
      (node (ref "R7") (pin "1") (pinfunction "1_1") (pintype "passive"))
      (node (ref "U1") (pin "8") (pinfunction "VBUS_8") (pintype "passive"))
    )
    (net (code "78") (name "Net-(USB1-CC1)") (class "Default")
      (node (ref "R18") (pin "2") (pinfunction "2_2") (pintype "passive"))
      (node (ref "USB1") (pin "A5") (pinfunction "CC1_A5") (pintype "passive"))
    )
    (net (code "79") (name "Net-(USB1-CC2)") (class "Default")
      (node (ref "R17") (pin "2") (pinfunction "2_2") (pintype "passive"))
      (node (ref "USB1") (pin "B5") (pinfunction "CC2_B5") (pintype "passive"))
    )
    (net (code "80") (name "unconnected-(J5-CD-Pad9)") (class "Default")
      (node (ref "J5") (pin "9") (pinfunction "CD_9") (pintype "passive+no_connect"))
    )
    (net (code "81") (name "unconnected-(J8-N.C.-Pad5)") (class "Default")
      (node (ref "J8") (pin "5") (pinfunction "N.C._5") (pintype "passive+no_connect"))
    )
    (net (code "82") (name "unconnected-(J8-N.C.-Pad6)") (class "Default")
      (node (ref "J8") (pin "6") (pinfunction "N.C._6") (pintype "passive+no_connect"))
    )
    (net (code "83") (name "unconnected-(J8-N.C.-Pad12)") (class "Default")
      (node (ref "J8") (pin "12") (pinfunction "N.C._12") (pintype "passive+no_connect"))
    )
    (net (code "84") (name "unconnected-(J8-N.C.-Pad13)") (class "Default")
      (node (ref "J8") (pin "13") (pinfunction "N.C._13") (pintype "passive+no_connect"))
    )
    (net (code "85") (name "unconnected-(U1-CHR0-Pad15)") (class "Default")
      (node (ref "U1") (pin "15") (pinfunction "CHR0_15") (pintype "passive+no_connect"))
    )
    (net (code "86") (name "unconnected-(U1-CHR1-Pad14)") (class "Default")
      (node (ref "U1") (pin "14") (pinfunction "CHR1_14") (pintype "passive+no_connect"))
    )
    (net (code "87") (name "unconnected-(U1-CHREN-Pad13)") (class "Default")
      (node (ref "U1") (pin "13") (pinfunction "CHREN_13") (pintype "passive+no_connect"))
    )
    (net (code "88") (name "unconnected-(U1-CTS-Pad23)") (class "Default")
      (node (ref "U1") (pin "23") (pinfunction "CTS_23") (pintype "passive+no_connect"))
    )
    (net (code "89") (name "unconnected-(U1-DCD-Pad1)") (class "Default")
      (node (ref "U1") (pin "1") (pinfunction "DCD_1") (pintype "passive+no_connect"))
    )
    (net (code "90") (name "unconnected-(U1-DSR-Pad27)") (class "Default")
      (node (ref "U1") (pin "27") (pinfunction "DSR_27") (pintype "passive+no_connect"))
    )
    (net (code "91") (name "unconnected-(U1-GPIO.0{slash}TXT-Pad19)") (class "Default")
      (node (ref "U1") (pin "19") (pinfunction "GPIO.0/TXT_19") (pintype "passive+no_connect"))
    )
    (net (code "92") (name "unconnected-(U1-GPIO.1{slash}RXT-Pad18)") (class "Default")
      (node (ref "U1") (pin "18") (pinfunction "GPIO.1/RXT_18") (pintype "passive+no_connect"))
    )
    (net (code "93") (name "unconnected-(U1-GPIO.2{slash}RS485-Pad17)") (class "Default")
      (node (ref "U1") (pin "17") (pinfunction "GPIO.2/RS485_17") (pintype "passive+no_connect"))
    )
    (net (code "94") (name "unconnected-(U1-GPIO.3{slash}WAKEUP-Pad16)") (class "Default")
      (node (ref "U1") (pin "16") (pinfunction "GPIO.3/WAKEUP_16") (pintype "passive+no_connect"))
    )
    (net (code "95") (name "unconnected-(U1-GPIO.4-Pad22)") (class "Default")
      (node (ref "U1") (pin "22") (pinfunction "GPIO.4_22") (pintype "passive+no_connect"))
    )
    (net (code "96") (name "unconnected-(U1-GPIO.5-Pad21)") (class "Default")
      (node (ref "U1") (pin "21") (pinfunction "GPIO.5_21") (pintype "passive+no_connect"))
    )
    (net (code "97") (name "unconnected-(U1-GPIO.6-Pad20)") (class "Default")
      (node (ref "U1") (pin "20") (pinfunction "GPIO.6_20") (pintype "passive+no_connect"))
    )
    (net (code "98") (name "unconnected-(U1-NC-Pad10)") (class "Default")
      (node (ref "U1") (pin "10") (pinfunction "NC_10") (pintype "passive+no_connect"))
    )
    (net (code "99") (name "unconnected-(U1-RI{slash}CLK-Pad2)") (class "Default")
      (node (ref "U1") (pin "2") (pinfunction "RI/CLK_2") (pintype "passive+no_connect"))
    )
    (net (code "100") (name "unconnected-(U1-SUSPEND-Pad12)") (class "Default")
      (node (ref "U1") (pin "12") (pinfunction "SUSPEND_12") (pintype "passive+no_connect"))
    )
    (net (code "101") (name "unconnected-(U4-B0-Pad18)") (class "Default")
      (node (ref "U4") (pin "18") (pinfunction "B0_18") (pintype "passive+no_connect"))
    )
    (net (code "102") (name "unconnected-(U4-B1-Pad17)") (class "Default")
      (node (ref "U4") (pin "17") (pinfunction "B1_17") (pintype "passive+no_connect"))
    )
    (net (code "103") (name "unconnected-(USB1-SBU1-PadA8)") (class "Default")
      (node (ref "USB1") (pin "A8") (pinfunction "SBU1_A8") (pintype "passive+no_connect"))
    )
    (net (code "104") (name "unconnected-(USB1-SBU2-PadB8)") (class "Default")
      (node (ref "USB1") (pin "B8") (pinfunction "SBU2_B8") (pintype "passive+no_connect"))
    )
  )
)
